# Sheet1.net
KiCad netlist of a schematic drawn in Altium Designer
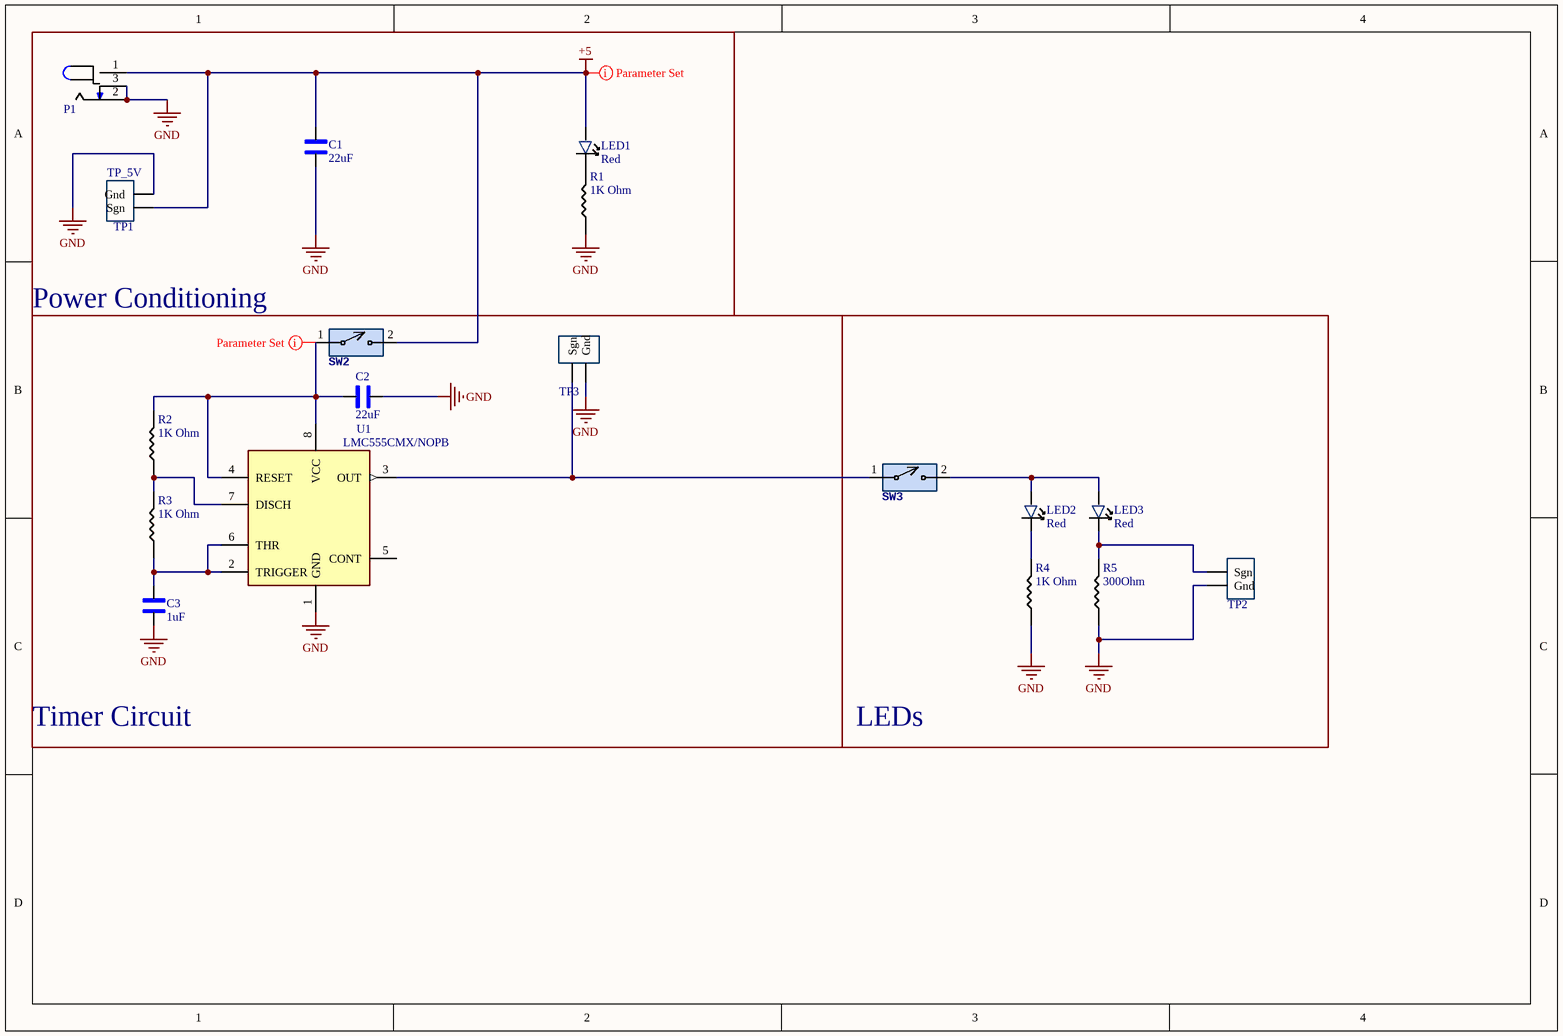
[diagram p0: Sheet1.SchDoc]

(export (version "E")
  (design (tool "Eeschema 10.0.6"))
  (components
    (comp (ref "C1")
      (value "22uF")
      (footprint "1206_Passive_Capacitor")
      (description "22uF ±10% 25V X5R 1206 Multilayer Ceramic Capacitors MLCC - SMD/SMT RoHS")
      (fields (field (name "MFR PART #") "CL31A226KAHNNNE") (field (name "LCSC PART#") "C12891"))
      (libsource (lib "ECEN5730Lib_2023_05_DS (1)") (part "C_22uF_1206"))
    )
    (comp (ref "C2")
      (value "22uF")
      (footprint "1206_Passive_Capacitor")
      (description "22uF ±10% 25V X5R 1206 Multilayer Ceramic Capacitors MLCC - SMD/SMT RoHS")
      (fields (field (name "MFR PART #") "CL31A226KAHNNNE") (field (name "LCSC PART#") "C12891"))
      (libsource (lib "ECEN5730Lib_2023_05_DS (1)") (part "C_22uF_1206"))
    )
    (comp (ref "C3")
      (value "1uF")
      (footprint "0402_Passive_Capacitor")
      (description "MULTILAYER CERAMIC CAPACITORS MLCC - SMD/SMT 1UF 25V 0402 ROHS")
      (fields (field (name "MFR PART #") "CL05A105KA5NQNC") (field (name "LCSC PART#") "C52923"))
      (libsource (lib "ECEN5730Lib_2023_05_DS (1)") (part "C_1uF_0402"))
    )
    (comp (ref "LED1")
      (value "Red")
      (footprint "LED_1206")
      (description "Red 621~631nm 1206 Light Emitting Diodes (LED) RoHS")
      (fields (field (name "MFR PART #") "15-21/R6C-FQ1R1B/2T") (field (name "LCSC PART#") "C93133"))
      (libsource (lib "ECEN5730Lib_2023_05_DS (1)") (part "LED_RED_1206"))
    )
    (comp (ref "LED2")
      (value "Red")
      (footprint "LED_1206")
      (description "Red 621~631nm 1206 Light Emitting Diodes (LED) RoHS")
      (fields (field (name "MFR PART #") "15-21/R6C-FQ1R1B/2T") (field (name "LCSC PART#") "C93133"))
      (libsource (lib "ECEN5730Lib_2023_05_DS (1)") (part "LED_RED_1206"))
    )
    (comp (ref "LED3")
      (value "Red")
      (footprint "LED_1206")
      (description "Red 621~631nm 1206 Light Emitting Diodes (LED) RoHS")
      (fields (field (name "MFR PART #") "15-21/R6C-FQ1R1B/2T") (field (name "LCSC PART#") "C93133"))
      (libsource (lib "ECEN5730Lib_2023_05_DS (1)") (part "LED_RED_1206"))
    )
    (comp (ref "P1")
      (value "Power Jack")
      (footprint "Power_Jack")
      (description "Power Barrel Connector Jack 2.10mm ID (0.083\"), 5.50mm OD (0.217\") Through Hole, Right Angle")
      (fields (field (name "MFR PART #") "PJ-102A") (field (name "LCSC PART#") "C136744"))
      (libsource (lib "ECEN5730Lib_2023_05_DS (1)") (part "P_Power Jack"))
    )
    (comp (ref "R1")
      (value "1K Ohm")
      (footprint "1206_Passive_Resitor")
      (description "CHIP RESISTOR - SURFACE MOUNT 1KOHMS ±1% 1/4W 1206 ROHS")
      (fields (field (name "MFR PART #") "RNCP1206FTD1K00CT") (field (name "LCSC PART#") "C4410"))
      (libsource (lib "ECEN5730Lib_2023_05_DS (1)") (part "R_1K_1206"))
    )
    (comp (ref "R2")
      (value "1K Ohm")
      (footprint "1206_Passive_Resitor")
      (description "CHIP RESISTOR - SURFACE MOUNT 1KOHMS ±1% 1/4W 1206 ROHS")
      (fields (field (name "MFR PART #") "RNCP1206FTD1K00CT") (field (name "LCSC PART#") "C4410"))
      (libsource (lib "ECEN5730Lib_2023_05_DS (1)") (part "R_1K_1206"))
    )
    (comp (ref "R3")
      (value "1K Ohm")
      (footprint "1206_Passive_Resitor")
      (description "CHIP RESISTOR - SURFACE MOUNT 1KOHMS ±1% 1/4W 1206 ROHS")
      (fields (field (name "MFR PART #") "RNCP1206FTD1K00CT") (field (name "LCSC PART#") "C4410"))
      (libsource (lib "ECEN5730Lib_2023_05_DS (1)") (part "R_1K_1206"))
    )
    (comp (ref "R4")
      (value "1K Ohm")
      (footprint "1206_Passive_Resitor")
      (description "CHIP RESISTOR - SURFACE MOUNT 1KOHMS ±1% 1/4W 1206 ROHS")
      (fields (field (name "MFR PART #") "RNCP1206FTD1K00CT") (field (name "LCSC PART#") "C4410"))
      (libsource (lib "ECEN5730Lib_2023_05_DS (1)") (part "R_1K_1206"))
    )
    (comp (ref "R5")
      (value "300Ohm")
      (footprint "1206_Passive_Resitor")
      (description "CHIP RESISTOR - SURFACE MOUNT 300OHMS ±1% 1/4W 1206 ROHS")
      (fields (field (name "MFR PART #") "1206W4F3000T5E") (field (name "LCSC PART#") "C17887"))
      (libsource (lib "ECEN5730Lib_2023_05_DS (1)") (part "R_300Ohm_1206"))
    )
    (comp (ref "SW2")
      (value "SW_2Pin_100mil_Switch")
      (footprint "2Pin-Header-Conn")
      (description "2Pin Header")
      (fields (field (name "LCSC PART#") "C124375"))
      (libsource (lib "ECEN5730Lib_2023_05_DS (1)") (part "SW_2Pin_100mil_Switch"))
    )
    (comp (ref "SW3")
      (value "SW_2Pin_100mil_Switch")
      (footprint "2Pin-Header-Conn")
      (description "2Pin Header")
      (fields (field (name "LCSC PART#") "C124375"))
      (libsource (lib "ECEN5730Lib_2023_05_DS (1)") (part "SW_2Pin_100mil_Switch"))
    )
    (comp (ref "TP1")
      (value "TP_5V")
      (footprint "TP10x_Probe")
      (description "Test Point 300 mil centers")
      (libsource (lib "ECEN5730Lib_2023_05_DS (1)") (part "TP_10x_Probe"))
    )
    (comp (ref "TP2")
      (value "10x Probe TP")
      (footprint "TP10x_Probe")
      (description "Test Point 300 mil centers")
      (libsource (lib "") (part "TP_10x_Probe_2"))
    )
    (comp (ref "TP3")
      (value "10x Probe TP")
      (footprint "TP10x_Probe")
      (description "Test Point 300 mil centers")
      (libsource (lib "") (part "TP_10x_Probe_1"))
    )
    (comp (ref "U1")
      (value "LMC555CMX/NOPB")
      (footprint "TS555IDTTR")
      (description "555 Type, Timer/Oscillator _Single_ IC 3MHz 8-SO")
      (fields (field (name "LCSC PART#") "C90760"))
      (libsource (lib "ECEN5730Lib_2023_05_DS (1)") (part "U_555_Fast"))
    )
  )
  (nets
    (net (code "1") (name "+5") (class "Default")
      (node (ref "C1") (pin "2") (pinfunction "2_2") (pintype "passive"))
      (node (ref "LED1") (pin "1") (pinfunction "1_1") (pintype "passive"))
      (node (ref "P1") (pin "1") (pinfunction "1_1") (pintype "power_in"))
      (node (ref "SW2") (pin "2") (pinfunction "2_2") (pintype "passive"))
      (node (ref "TP1") (pin "1") (pinfunction "Sgn_1") (pintype "passive"))
    )
    (net (code "2") (name "GND") (class "Default")
      (node (ref "C1") (pin "1") (pinfunction "1_1") (pintype "passive"))
      (node (ref "C2") (pin "2") (pinfunction "2_2") (pintype "passive"))
      (node (ref "C3") (pin "1") (pinfunction "1_1") (pintype "passive"))
      (node (ref "P1") (pin "2") (pinfunction "2_2") (pintype "power_in"))
      (node (ref "P1") (pin "3") (pinfunction "3_3") (pintype "power_in"))
      (node (ref "R1") (pin "1") (pinfunction "1_1") (pintype "passive"))
      (node (ref "R4") (pin "1") (pinfunction "1_1") (pintype "passive"))
      (node (ref "R5") (pin "1") (pinfunction "1_1") (pintype "passive"))
      (node (ref "TP1") (pin "2") (pinfunction "Gnd_2") (pintype "passive"))
      (node (ref "TP2") (pin "2") (pinfunction "Gnd_2") (pintype "passive"))
      (node (ref "TP3") (pin "2") (pinfunction "Gnd_2") (pintype "passive"))
      (node (ref "U1") (pin "1") (pinfunction "GND_1") (pintype "power_in"))
    )
    (net (code "3") (name "Net-(LED1-Pad2)") (class "Default")
      (node (ref "LED1") (pin "2") (pinfunction "2_2") (pintype "passive"))
      (node (ref "R1") (pin "2") (pinfunction "2_2") (pintype "passive"))
    )
    (net (code "4") (name "Net-(LED2-Pad1)") (class "Default")
      (node (ref "LED2") (pin "1") (pinfunction "1_1") (pintype "passive"))
      (node (ref "LED3") (pin "1") (pinfunction "1_1") (pintype "passive"))
      (node (ref "SW3") (pin "2") (pinfunction "2_2") (pintype "passive"))
    )
    (net (code "5") (name "Net-(LED2-Pad2)") (class "Default")
      (node (ref "LED2") (pin "2") (pinfunction "2_2") (pintype "passive"))
      (node (ref "R4") (pin "2") (pinfunction "2_2") (pintype "passive"))
    )
    (net (code "6") (name "Net-(TP2-Sgn)") (class "Default")
      (node (ref "LED3") (pin "2") (pinfunction "2_2") (pintype "passive"))
      (node (ref "R5") (pin "2") (pinfunction "2_2") (pintype "passive"))
      (node (ref "TP2") (pin "1") (pinfunction "Sgn_1") (pintype "passive"))
    )
    (net (code "7") (name "Net-(TP3-Sgn)") (class "Default")
      (node (ref "SW3") (pin "1") (pinfunction "1_1") (pintype "passive"))
      (node (ref "TP3") (pin "1") (pinfunction "Sgn_1") (pintype "passive"))
      (node (ref "U1") (pin "3") (pinfunction "OUT_3") (pintype "output"))
    )
    (net (code "8") (name "Net-(U1-DISCH)") (class "Default")
      (node (ref "R2") (pin "1") (pinfunction "1_1") (pintype "passive"))
      (node (ref "R3") (pin "2") (pinfunction "2_2") (pintype "passive"))
      (node (ref "U1") (pin "7") (pinfunction "DISCH_7") (pintype "passive"))
    )
    (net (code "9") (name "Net-(U1-RESET)") (class "Default")
      (node (ref "C2") (pin "1") (pinfunction "1_1") (pintype "passive"))
      (node (ref "R2") (pin "2") (pinfunction "2_2") (pintype "passive"))
      (node (ref "SW2") (pin "1") (pinfunction "1_1") (pintype "passive"))
      (node (ref "U1") (pin "4") (pinfunction "RESET_4") (pintype "passive"))
      (node (ref "U1") (pin "8") (pinfunction "VCC_8") (pintype "power_in"))
    )
    (net (code "10") (name "Net-(U1-THR)") (class "Default")
      (node (ref "C3") (pin "2") (pinfunction "2_2") (pintype "passive"))
      (node (ref "R3") (pin "1") (pinfunction "1_1") (pintype "passive"))
      (node (ref "U1") (pin "2") (pinfunction "TRIGGER_2") (pintype "passive"))
      (node (ref "U1") (pin "6") (pinfunction "THR_6") (pintype "passive"))
    )
    (net (code "11") (name "unconnected-(U1-CONT-Pad5)") (class "Default")
      (node (ref "U1") (pin "5") (pinfunction "CONT_5") (pintype "passive"))
    )
  )
)
